# v002.net
KiCad netlist of a schematic drawn in EAGLE
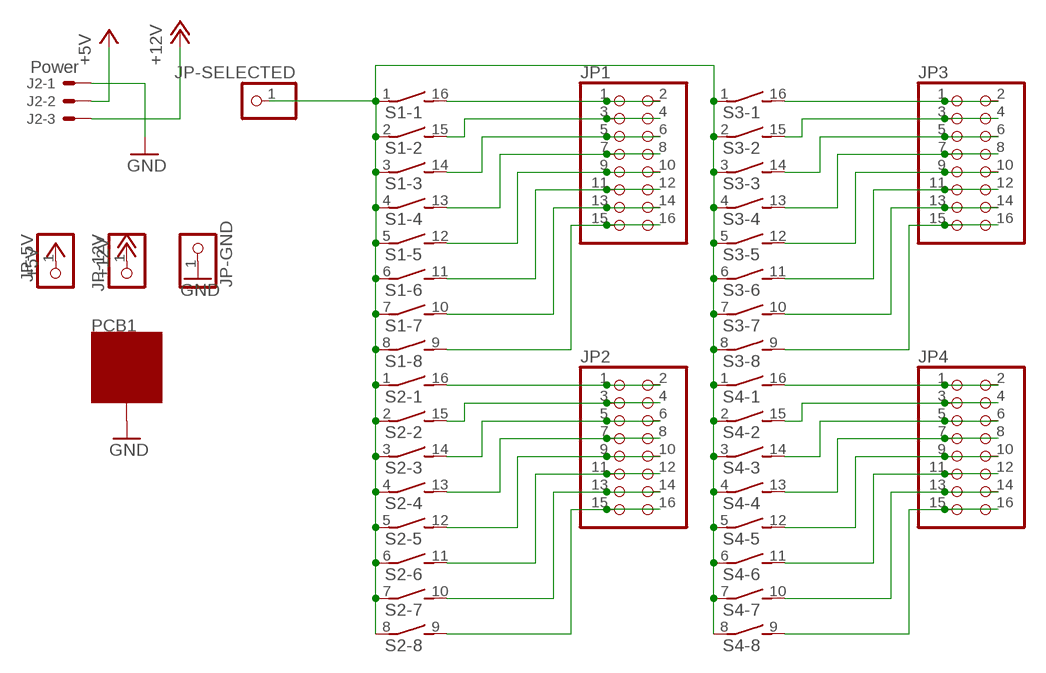
[diagram p0: schematic, sheet 1]

(export (version "E")
  (design (tool "Eeschema 10.0.6"))
  (components
    (comp (ref "J2")
      (value "Power")
      (footprint "eagle-import:6410-03")
      (libsource (lib "eagle-import") (part "22-?-0327-2031"))
    )
    (comp (ref "JP-5V")
      (value "PINHD-1X1")
      (footprint "eagle-import:1X01")
      (libsource (lib "eagle-import") (part "PINHD-1X1"))
    )
    (comp (ref "JP-12V")
      (value "PINHD-1X1")
      (footprint "eagle-import:1X01")
      (libsource (lib "eagle-import") (part "PINHD-1X1"))
    )
    (comp (ref "JP-GND")
      (value "PINHD-1X1")
      (footprint "eagle-import:1X01")
      (libsource (lib "eagle-import") (part "PINHD-1X1"))
    )
    (comp (ref "JP-SELECTED")
      (value "PINHD-1X1")
      (footprint "eagle-import:1X01")
      (libsource (lib "eagle-import") (part "PINHD-1X1"))
    )
    (comp (ref "JP1")
      (value "PINHD-2X8")
      (footprint "eagle-import:2X08")
      (libsource (lib "eagle-import") (part "PINHD-2X8"))
    )
    (comp (ref "JP2")
      (value "PINHD-2X8")
      (footprint "eagle-import:2X08")
      (libsource (lib "eagle-import") (part "PINHD-2X8"))
    )
    (comp (ref "JP3")
      (value "PINHD-2X8")
      (footprint "eagle-import:2X08")
      (libsource (lib "eagle-import") (part "PINHD-2X8"))
    )
    (comp (ref "JP4")
      (value "PINHD-2X8")
      (footprint "eagle-import:2X08")
      (libsource (lib "eagle-import") (part "PINHD-2X8"))
    )
    (comp (ref "PCB1")
      (value "ZZZ_MODULE05X05")
      (footprint "eagle-import:ZZZ_MODULE_05X05")
      (libsource (lib "eagle-import") (part "ZZZ_MODULE05X05"))
    )
    (comp (ref "S1")
      (value "DIP08S")
      (footprint "eagle-import:DIP08S")
      (libsource (lib "eagle-import") (part "DIP08S"))
    )
    (comp (ref "S2")
      (value "DIP08S")
      (footprint "eagle-import:DIP08S")
      (libsource (lib "eagle-import") (part "DIP08S"))
    )
    (comp (ref "S3")
      (value "DIP08S")
      (footprint "eagle-import:DIP08S")
      (libsource (lib "eagle-import") (part "DIP08S"))
    )
    (comp (ref "S4")
      (value "DIP08S")
      (footprint "eagle-import:DIP08S")
      (libsource (lib "eagle-import") (part "DIP08S"))
    )
  )
  (nets
    (net (code "1") (name "+5V") (class "Default")
      (node (ref "J2") (pin "2") (pinfunction "S_2") (pintype "passive"))
      (node (ref "JP-5V") (pin "1") (pinfunction "1_1") (pintype "passive"))
    )
    (net (code "2") (name "+12V") (class "Default")
      (node (ref "J2") (pin "3") (pinfunction "S_3") (pintype "passive"))
      (node (ref "JP-12V") (pin "1") (pinfunction "1_1") (pintype "passive"))
    )
    (net (code "3") (name "GND") (class "Default")
      (node (ref "J2") (pin "1") (pinfunction "S_1") (pintype "passive"))
      (node (ref "JP-GND") (pin "1") (pinfunction "1_1") (pintype "passive"))
      (node (ref "PCB1") (pin "GND@1") (pinfunction "GND_GND@1") (pintype "power_in"))
      (node (ref "PCB1") (pin "GND@2") (pinfunction "GND_GND@2") (pintype "power_in"))
      (node (ref "PCB1") (pin "GND@3") (pinfunction "GND_GND@3") (pintype "power_in"))
      (node (ref "PCB1") (pin "GND@4") (pinfunction "GND_GND@4") (pintype "power_in"))
      (node (ref "PCB1") (pin "GND@5") (pinfunction "GND_GND@5") (pintype "power_in"))
      (node (ref "PCB1") (pin "GND@6") (pinfunction "GND_GND@6") (pintype "power_in"))
      (node (ref "PCB1") (pin "GND@7") (pinfunction "GND_GND@7") (pintype "power_in"))
      (node (ref "PCB1") (pin "GND@8") (pinfunction "GND_GND@8") (pintype "power_in"))
    )
    (net (code "4") (name "Net-(S1A-2)") (class "Default")
      (node (ref "JP1") (pin "1") (pinfunction "1_1") (pintype "passive"))
      (node (ref "JP1") (pin "2") (pinfunction "2_2") (pintype "passive"))
      (node (ref "S1") (pin "16") (pinfunction "2_16") (pintype "passive"))
    )
    (net (code "5") (name "Net-(S1B-1)") (class "Default")
      (node (ref "JP-SELECTED") (pin "1") (pinfunction "1_1") (pintype "passive"))
      (node (ref "S1") (pin "1") (pinfunction "1_1") (pintype "passive"))
      (node (ref "S1") (pin "2") (pinfunction "1_2") (pintype "passive"))
      (node (ref "S1") (pin "3") (pinfunction "1_3") (pintype "passive"))
      (node (ref "S1") (pin "4") (pinfunction "1_4") (pintype "passive"))
      (node (ref "S1") (pin "5") (pinfunction "1_5") (pintype "passive"))
      (node (ref "S1") (pin "6") (pinfunction "1_6") (pintype "passive"))
      (node (ref "S1") (pin "7") (pinfunction "1_7") (pintype "passive"))
      (node (ref "S1") (pin "8") (pinfunction "1_8") (pintype "passive"))
      (node (ref "S2") (pin "1") (pinfunction "1_1") (pintype "passive"))
      (node (ref "S2") (pin "2") (pinfunction "1_2") (pintype "passive"))
      (node (ref "S2") (pin "3") (pinfunction "1_3") (pintype "passive"))
      (node (ref "S2") (pin "4") (pinfunction "1_4") (pintype "passive"))
      (node (ref "S2") (pin "5") (pinfunction "1_5") (pintype "passive"))
      (node (ref "S2") (pin "6") (pinfunction "1_6") (pintype "passive"))
      (node (ref "S2") (pin "7") (pinfunction "1_7") (pintype "passive"))
      (node (ref "S2") (pin "8") (pinfunction "1_8") (pintype "passive"))
      (node (ref "S3") (pin "1") (pinfunction "1_1") (pintype "passive"))
      (node (ref "S3") (pin "2") (pinfunction "1_2") (pintype "passive"))
      (node (ref "S3") (pin "3") (pinfunction "1_3") (pintype "passive"))
      (node (ref "S3") (pin "4") (pinfunction "1_4") (pintype "passive"))
      (node (ref "S3") (pin "5") (pinfunction "1_5") (pintype "passive"))
      (node (ref "S3") (pin "6") (pinfunction "1_6") (pintype "passive"))
      (node (ref "S3") (pin "7") (pinfunction "1_7") (pintype "passive"))
      (node (ref "S3") (pin "8") (pinfunction "1_8") (pintype "passive"))
      (node (ref "S4") (pin "1") (pinfunction "1_1") (pintype "passive"))
      (node (ref "S4") (pin "2") (pinfunction "1_2") (pintype "passive"))
      (node (ref "S4") (pin "3") (pinfunction "1_3") (pintype "passive"))
      (node (ref "S4") (pin "4") (pinfunction "1_4") (pintype "passive"))
      (node (ref "S4") (pin "5") (pinfunction "1_5") (pintype "passive"))
      (node (ref "S4") (pin "6") (pinfunction "1_6") (pintype "passive"))
      (node (ref "S4") (pin "7") (pinfunction "1_7") (pintype "passive"))
      (node (ref "S4") (pin "8") (pinfunction "1_8") (pintype "passive"))
    )
    (net (code "6") (name "Net-(S1B-2)") (class "Default")
      (node (ref "JP1") (pin "3") (pinfunction "3_3") (pintype "passive"))
      (node (ref "JP1") (pin "4") (pinfunction "4_4") (pintype "passive"))
      (node (ref "S1") (pin "15") (pinfunction "2_15") (pintype "passive"))
    )
    (net (code "7") (name "Net-(S1C-2)") (class "Default")
      (node (ref "JP1") (pin "5") (pinfunction "5_5") (pintype "passive"))
      (node (ref "JP1") (pin "6") (pinfunction "6_6") (pintype "passive"))
      (node (ref "S1") (pin "14") (pinfunction "2_14") (pintype "passive"))
    )
    (net (code "8") (name "Net-(S1D-2)") (class "Default")
      (node (ref "JP1") (pin "7") (pinfunction "7_7") (pintype "passive"))
      (node (ref "JP1") (pin "8") (pinfunction "8_8") (pintype "passive"))
      (node (ref "S1") (pin "13") (pinfunction "2_13") (pintype "passive"))
    )
    (net (code "9") (name "Net-(S1E-2)") (class "Default")
      (node (ref "JP1") (pin "10") (pinfunction "10_10") (pintype "passive"))
      (node (ref "JP1") (pin "9") (pinfunction "9_9") (pintype "passive"))
      (node (ref "S1") (pin "12") (pinfunction "2_12") (pintype "passive"))
    )
    (net (code "10") (name "Net-(S1F-2)") (class "Default")
      (node (ref "JP1") (pin "11") (pinfunction "11_11") (pintype "passive"))
      (node (ref "JP1") (pin "12") (pinfunction "12_12") (pintype "passive"))
      (node (ref "S1") (pin "11") (pinfunction "2_11") (pintype "passive"))
    )
    (net (code "11") (name "Net-(S1G-2)") (class "Default")
      (node (ref "JP1") (pin "13") (pinfunction "13_13") (pintype "passive"))
      (node (ref "JP1") (pin "14") (pinfunction "14_14") (pintype "passive"))
      (node (ref "S1") (pin "10") (pinfunction "2_10") (pintype "passive"))
    )
    (net (code "12") (name "Net-(S1H-2)") (class "Default")
      (node (ref "JP1") (pin "15") (pinfunction "15_15") (pintype "passive"))
      (node (ref "JP1") (pin "16") (pinfunction "16_16") (pintype "passive"))
      (node (ref "S1") (pin "9") (pinfunction "2_9") (pintype "passive"))
    )
    (net (code "13") (name "Net-(S2A-2)") (class "Default")
      (node (ref "JP2") (pin "1") (pinfunction "1_1") (pintype "passive"))
      (node (ref "JP2") (pin "2") (pinfunction "2_2") (pintype "passive"))
      (node (ref "S2") (pin "16") (pinfunction "2_16") (pintype "passive"))
    )
    (net (code "14") (name "Net-(S2B-2)") (class "Default")
      (node (ref "JP2") (pin "3") (pinfunction "3_3") (pintype "passive"))
      (node (ref "JP2") (pin "4") (pinfunction "4_4") (pintype "passive"))
      (node (ref "S2") (pin "15") (pinfunction "2_15") (pintype "passive"))
    )
    (net (code "15") (name "Net-(S2C-2)") (class "Default")
      (node (ref "JP2") (pin "5") (pinfunction "5_5") (pintype "passive"))
      (node (ref "JP2") (pin "6") (pinfunction "6_6") (pintype "passive"))
      (node (ref "S2") (pin "14") (pinfunction "2_14") (pintype "passive"))
    )
    (net (code "16") (name "Net-(S2D-2)") (class "Default")
      (node (ref "JP2") (pin "7") (pinfunction "7_7") (pintype "passive"))
      (node (ref "JP2") (pin "8") (pinfunction "8_8") (pintype "passive"))
      (node (ref "S2") (pin "13") (pinfunction "2_13") (pintype "passive"))
    )
    (net (code "17") (name "Net-(S2E-2)") (class "Default")
      (node (ref "JP2") (pin "10") (pinfunction "10_10") (pintype "passive"))
      (node (ref "JP2") (pin "9") (pinfunction "9_9") (pintype "passive"))
      (node (ref "S2") (pin "12") (pinfunction "2_12") (pintype "passive"))
    )
    (net (code "18") (name "Net-(S2F-2)") (class "Default")
      (node (ref "JP2") (pin "11") (pinfunction "11_11") (pintype "passive"))
      (node (ref "JP2") (pin "12") (pinfunction "12_12") (pintype "passive"))
      (node (ref "S2") (pin "11") (pinfunction "2_11") (pintype "passive"))
    )
    (net (code "19") (name "Net-(S2G-2)") (class "Default")
      (node (ref "JP2") (pin "13") (pinfunction "13_13") (pintype "passive"))
      (node (ref "JP2") (pin "14") (pinfunction "14_14") (pintype "passive"))
      (node (ref "S2") (pin "10") (pinfunction "2_10") (pintype "passive"))
    )
    (net (code "20") (name "Net-(S2H-2)") (class "Default")
      (node (ref "JP2") (pin "15") (pinfunction "15_15") (pintype "passive"))
      (node (ref "JP2") (pin "16") (pinfunction "16_16") (pintype "passive"))
      (node (ref "S2") (pin "9") (pinfunction "2_9") (pintype "passive"))
    )
    (net (code "21") (name "Net-(S3A-2)") (class "Default")
      (node (ref "JP3") (pin "1") (pinfunction "1_1") (pintype "passive"))
      (node (ref "JP3") (pin "2") (pinfunction "2_2") (pintype "passive"))
      (node (ref "S3") (pin "16") (pinfunction "2_16") (pintype "passive"))
    )
    (net (code "22") (name "Net-(S3B-2)") (class "Default")
      (node (ref "JP3") (pin "3") (pinfunction "3_3") (pintype "passive"))
      (node (ref "JP3") (pin "4") (pinfunction "4_4") (pintype "passive"))
      (node (ref "S3") (pin "15") (pinfunction "2_15") (pintype "passive"))
    )
    (net (code "23") (name "Net-(S3C-2)") (class "Default")
      (node (ref "JP3") (pin "5") (pinfunction "5_5") (pintype "passive"))
      (node (ref "JP3") (pin "6") (pinfunction "6_6") (pintype "passive"))
      (node (ref "S3") (pin "14") (pinfunction "2_14") (pintype "passive"))
    )
    (net (code "24") (name "Net-(S3D-2)") (class "Default")
      (node (ref "JP3") (pin "7") (pinfunction "7_7") (pintype "passive"))
      (node (ref "JP3") (pin "8") (pinfunction "8_8") (pintype "passive"))
      (node (ref "S3") (pin "13") (pinfunction "2_13") (pintype "passive"))
    )
    (net (code "25") (name "Net-(S3E-2)") (class "Default")
      (node (ref "JP3") (pin "10") (pinfunction "10_10") (pintype "passive"))
      (node (ref "JP3") (pin "9") (pinfunction "9_9") (pintype "passive"))
      (node (ref "S3") (pin "12") (pinfunction "2_12") (pintype "passive"))
    )
    (net (code "26") (name "Net-(S3F-2)") (class "Default")
      (node (ref "JP3") (pin "11") (pinfunction "11_11") (pintype "passive"))
      (node (ref "JP3") (pin "12") (pinfunction "12_12") (pintype "passive"))
      (node (ref "S3") (pin "11") (pinfunction "2_11") (pintype "passive"))
    )
    (net (code "27") (name "Net-(S3G-2)") (class "Default")
      (node (ref "JP3") (pin "13") (pinfunction "13_13") (pintype "passive"))
      (node (ref "JP3") (pin "14") (pinfunction "14_14") (pintype "passive"))
      (node (ref "S3") (pin "10") (pinfunction "2_10") (pintype "passive"))
    )
    (net (code "28") (name "Net-(S3H-2)") (class "Default")
      (node (ref "JP3") (pin "15") (pinfunction "15_15") (pintype "passive"))
      (node (ref "JP3") (pin "16") (pinfunction "16_16") (pintype "passive"))
      (node (ref "S3") (pin "9") (pinfunction "2_9") (pintype "passive"))
    )
    (net (code "29") (name "Net-(S4A-2)") (class "Default")
      (node (ref "JP4") (pin "1") (pinfunction "1_1") (pintype "passive"))
      (node (ref "JP4") (pin "2") (pinfunction "2_2") (pintype "passive"))
      (node (ref "S4") (pin "16") (pinfunction "2_16") (pintype "passive"))
    )
    (net (code "30") (name "Net-(S4B-2)") (class "Default")
      (node (ref "JP4") (pin "3") (pinfunction "3_3") (pintype "passive"))
      (node (ref "JP4") (pin "4") (pinfunction "4_4") (pintype "passive"))
      (node (ref "S4") (pin "15") (pinfunction "2_15") (pintype "passive"))
    )
    (net (code "31") (name "Net-(S4C-2)") (class "Default")
      (node (ref "JP4") (pin "5") (pinfunction "5_5") (pintype "passive"))
      (node (ref "JP4") (pin "6") (pinfunction "6_6") (pintype "passive"))
      (node (ref "S4") (pin "14") (pinfunction "2_14") (pintype "passive"))
    )
    (net (code "32") (name "Net-(S4D-2)") (class "Default")
      (node (ref "JP4") (pin "7") (pinfunction "7_7") (pintype "passive"))
      (node (ref "JP4") (pin "8") (pinfunction "8_8") (pintype "passive"))
      (node (ref "S4") (pin "13") (pinfunction "2_13") (pintype "passive"))
    )
    (net (code "33") (name "Net-(S4E-2)") (class "Default")
      (node (ref "JP4") (pin "10") (pinfunction "10_10") (pintype "passive"))
      (node (ref "JP4") (pin "9") (pinfunction "9_9") (pintype "passive"))
      (node (ref "S4") (pin "12") (pinfunction "2_12") (pintype "passive"))
    )
    (net (code "34") (name "Net-(S4F-2)") (class "Default")
      (node (ref "JP4") (pin "11") (pinfunction "11_11") (pintype "passive"))
      (node (ref "JP4") (pin "12") (pinfunction "12_12") (pintype "passive"))
      (node (ref "S4") (pin "11") (pinfunction "2_11") (pintype "passive"))
    )
    (net (code "35") (name "Net-(S4G-2)") (class "Default")
      (node (ref "JP4") (pin "13") (pinfunction "13_13") (pintype "passive"))
      (node (ref "JP4") (pin "14") (pinfunction "14_14") (pintype "passive"))
      (node (ref "S4") (pin "10") (pinfunction "2_10") (pintype "passive"))
    )
    (net (code "36") (name "Net-(S4H-2)") (class "Default")
      (node (ref "JP4") (pin "15") (pinfunction "15_15") (pintype "passive"))
      (node (ref "JP4") (pin "16") (pinfunction "16_16") (pintype "passive"))
      (node (ref "S4") (pin "9") (pinfunction "2_9") (pintype "passive"))
    )
  )
)
